# programmable-xtal-breakout.net
KiCad netlist of a schematic drawn in EAGLE
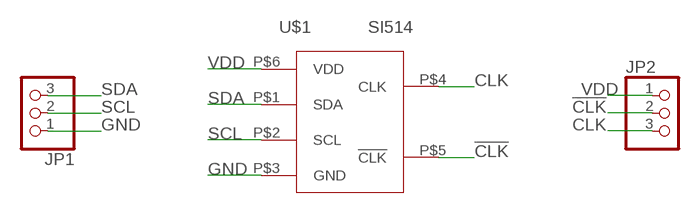
[diagram p0: schematic, sheet 1]

(export (version "E")
  (design (tool "Eeschema 10.0.6"))
  (components
    (comp (ref "JP1")
      (value "PINHD-1X3")
      (footprint "eagle-import:1X03")
      (libsource (lib "eagle-import") (part "PINHD-1X3"))
    )
    (comp (ref "JP2")
      (value "PINHD-1X3")
      (footprint "eagle-import:1X03")
      (libsource (lib "eagle-import") (part "PINHD-1X3"))
    )
    (comp (ref "U$1")
      (value "SI514")
      (footprint "eagle-import:XTAL-6PIN")
      (libsource (lib "eagle-import") (part "SI514"))
    )
  )
  (nets
    (net (code "1") (name "/CLK") (class "Default")
      (node (ref "JP2") (pin "3") (pinfunction "3_3") (pintype "passive"))
      (node (ref "U$1") (pin "P$4") (pinfunction "CLK_P$4") (pintype "bidirectional"))
    )
    (net (code "2") (name "/GND") (class "Default")
      (node (ref "JP1") (pin "1") (pinfunction "1_1") (pintype "passive"))
      (node (ref "U$1") (pin "P$3") (pinfunction "GND_P$3") (pintype "bidirectional"))
    )
    (net (code "3") (name "/SCL") (class "Default")
      (node (ref "JP1") (pin "2") (pinfunction "2_2") (pintype "passive"))
      (node (ref "U$1") (pin "P$2") (pinfunction "SCL_P$2") (pintype "bidirectional"))
    )
    (net (code "4") (name "/SDA") (class "Default")
      (node (ref "JP1") (pin "3") (pinfunction "3_3") (pintype "passive"))
      (node (ref "U$1") (pin "P$1") (pinfunction "SDA_P$1") (pintype "bidirectional"))
    )
    (net (code "5") (name "/VDD") (class "Default")
      (node (ref "JP2") (pin "1") (pinfunction "1_1") (pintype "passive"))
      (node (ref "U$1") (pin "P$6") (pinfunction "VDD_P$6") (pintype "bidirectional"))
    )
    (net (code "6") (name "/~{CLK}") (class "Default")
      (node (ref "JP2") (pin "2") (pinfunction "2_2") (pintype "passive"))
      (node (ref "U$1") (pin "P$5") (pinfunction "~{CLK}_P$5") (pintype "bidirectional"))
    )
  )
)
